# Power.net
KiCad netlist of a schematic drawn in Altium Designer
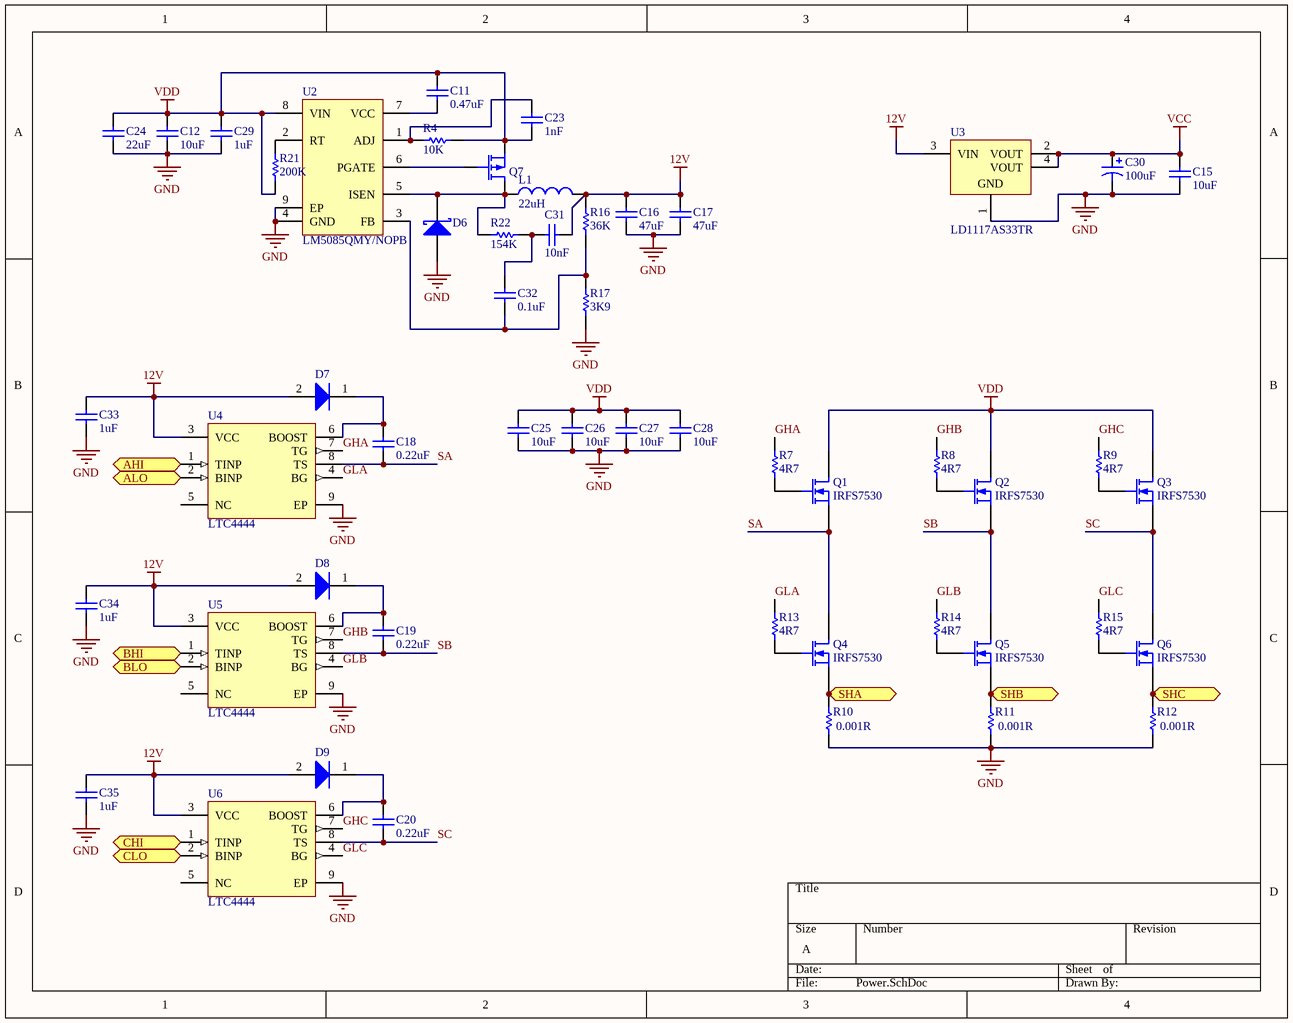
[diagram p0: Power.SchDoc]

(export (version "E")
  (design (tool "Eeschema 10.0.6"))
  (components
    (comp (ref "C11")
      (value "0.47uF")
      (footprint "CAPC0603(1608)100_N")
      (description "CAP 470nF 50V ±10% 0603 (1608 Metric) Thickness 1mm SMD")
      (fields (field (name "TOLERANCE") "Â±10%"))
      (libsource (lib "Altium Content Vault") (part "CAP"))
    )
    (comp (ref "C12")
      (value "10uF")
      (footprint "CAPC1206(3216)190_M")
      (description "CAP 10uF 50V Â±10% 1206 (3216 Metric) Thickness 1.9mm SMD")
      (fields (field (name "TOLERANCE") "Â±10%"))
      (libsource (lib "Altium Content Vault") (part "CMP-1037-04982-1"))
    )
    (comp (ref "C15")
      (value "10uF")
      (footprint "CAPC0402(1005)60_N")
      (description "CAP 10uF 6.3V ±20% 0402 (1005 Metric) Thickness 0.6mm SMD")
      (fields (field (name "TOLERANCE") "Â±20%"))
      (libsource (lib "Altium Content Vault") (part "CMP-1034-02138-1"))
    )
    (comp (ref "C16")
      (value "47uF")
      (footprint "CAPC1210(3225)280_N")
      (description "CAP 47uF 16V ±10% 1210 (3225 Metric) Thickness 2.8mm SMD")
      (fields (field (name "TOLERANCE") "Â±10%"))
      (libsource (lib "Altium Content Vault") (part "CAP"))
    )
    (comp (ref "C17")
      (value "47uF")
      (footprint "CAPC1210(3225)280_N")
      (description "CAP 47uF 16V ±10% 1210 (3225 Metric) Thickness 2.8mm SMD")
      (fields (field (name "TOLERANCE") "Â±10%"))
      (libsource (lib "Altium Content Vault") (part "CAP"))
    )
    (comp (ref "C18")
      (value "0.22uF")
      (footprint "CAPC0603(1608)100_N")
      (description "CAP 1uF 16V ±5% 0603 (1608 Metric) Thickness 1mm SMD")
      (fields (field (name "TOLERANCE") "Â±5%"))
      (libsource (lib "Altium Content Vault") (part "CMP-1035-02736-1"))
    )
    (comp (ref "C19")
      (value "0.22uF")
      (footprint "CAPC0603(1608)100_N")
      (description "CAP 1uF 16V ±5% 0603 (1608 Metric) Thickness 1mm SMD")
      (fields (field (name "TOLERANCE") "Â±5%"))
      (libsource (lib "Altium Content Vault") (part "CMP-1035-02736-1"))
    )
    (comp (ref "C20")
      (value "0.22uF")
      (footprint "CAPC0603(1608)100_N")
      (description "CAP 1uF 16V ±5% 0603 (1608 Metric) Thickness 1mm SMD")
      (fields (field (name "TOLERANCE") "Â±5%"))
      (libsource (lib "Altium Content Vault") (part "CMP-1035-02736-1"))
    )
    (comp (ref "C23")
      (value "1nF")
      (footprint "CAPC0402(1005)60_N")
      (description "CAP 1nF 50V ±1% 0402 (1005 Metric) Thickness 0.6mm SMD")
      (fields (field (name "TOLERANCE") "Â±1%"))
      (libsource (lib "Altium Content Vault") (part "CMP-1034-01624-1"))
    )
    (comp (ref "C24")
      (value "22uF")
      (footprint "CAPC2220(5750)230_N")
      (description "CAP 22uF 50V -20% to +80% 2220 (5750 Metric) Thickness 2.2mm SMD")
      (fields (field (name "TOLERANCE") "-20% to +80%"))
      (libsource (lib "Altium Content Vault") (part "CAP"))
    )
    (comp (ref "C25")
      (value "10uF")
      (footprint "CAPC1206(3216)190_M")
      (description "CAP 10uF 50V Â±10% 1206 (3216 Metric) Thickness 1.9mm SMD")
      (fields (field (name "TOLERANCE") "Â±10%"))
      (libsource (lib "Altium Content Vault") (part "CMP-1037-04982-1"))
    )
    (comp (ref "C26")
      (value "10uF")
      (footprint "CAPC1206(3216)190_M")
      (description "CAP 10uF 50V Â±10% 1206 (3216 Metric) Thickness 1.9mm SMD")
      (fields (field (name "TOLERANCE") "Â±10%"))
      (libsource (lib "Altium Content Vault") (part "CAP"))
    )
    (comp (ref "C27")
      (value "10uF")
      (footprint "CAPC1206(3216)190_M")
      (description "CAP 10uF 50V Â±10% 1206 (3216 Metric) Thickness 1.9mm SMD")
      (fields (field (name "TOLERANCE") "Â±10%"))
      (libsource (lib "Altium Content Vault") (part "CAP"))
    )
    (comp (ref "C28")
      (value "10uF")
      (footprint "CAPC1206(3216)190_M")
      (description "CAP 10uF 50V Â±10% 1206 (3216 Metric) Thickness 1.9mm SMD")
      (fields (field (name "TOLERANCE") "Â±10%"))
      (libsource (lib "Altium Content Vault") (part "CMP-1037-04982-1"))
    )
    (comp (ref "C29")
      (value "1uF")
      (footprint "CAPC0603(1608)100_L")
      (description "CAP 1uF 50V ±10% 0603 (1608 Metric) Thickness 1mm SMD")
      (fields (field (name "TOLERANCE") "Â±10%"))
      (libsource (lib "Altium Content Vault") (part "CAP"))
    )
    (comp (ref "C30")
      (value "100uF")
      (footprint "AVX-CAPC7343_V")
      (libsource (lib "Components") (part "AVX-CAP-P-2"))
    )
    (comp (ref "C31")
      (value "10nF")
      (footprint "CAPC0402(1005)60_L")
      (description "CAP 10nF 50V ±5% 0402 (1005 Metric) Thickness 0.6mm SMD")
      (fields (field (name "TOLERANCE") "Â±5%"))
      (libsource (lib "Altium Content Vault") (part "CAP"))
    )
    (comp (ref "C32")
      (value "0.1uF")
      (footprint "CAPC0402(1005)60_M")
      (description "CAP 100nF 50V ±10% 0402 (1005 Metric) Thickness 0.6mm SMD")
      (fields (field (name "TOLERANCE") "Â±10%"))
      (libsource (lib "Altium Content Vault") (part "CMP-1034-02077-1"))
    )
    (comp (ref "C33")
      (value "1uF")
      (footprint "CAPC0402(1005)60_M")
      (description "CAP 1uF 16V ±10% 0402 (1005 Metric) Thickness 0.6mm SMD")
      (fields (field (name "TOLERANCE") "Â±10%"))
      (libsource (lib "Altium Content Vault") (part "CMP-1034-02119-1"))
    )
    (comp (ref "C34")
      (value "1uF")
      (footprint "CAPC0402(1005)60_M")
      (description "CAP 1uF 16V ±10% 0402 (1005 Metric) Thickness 0.6mm SMD")
      (fields (field (name "TOLERANCE") "Â±10%"))
      (libsource (lib "Altium Content Vault") (part "CMP-1034-02119-1"))
    )
    (comp (ref "C35")
      (value "1uF")
      (footprint "CAPC0402(1005)60_M")
      (description "CAP 1uF 16V ±10% 0402 (1005 Metric) Thickness 0.6mm SMD")
      (fields (field (name "TOLERANCE") "Â±10%"))
      (libsource (lib "Altium Content Vault") (part "CMP-1034-02119-1"))
    )
    (comp (ref "D6")
      (value "~")
      (footprint "SMB")
      (description "Schottky Diode")
      (fields (field (name "PUBLISHER") "Altium Limited"))
      (libsource (lib "Miscellaneous Devices") (part "D Schottky"))
    )
    (comp (ref "D7")
      (value "~")
      (footprint "ONSC-SOD-323-2-477-02_V")
      (description "Silicon Hot-Carrier Diode, Schottky Barrier Diode, 2-Pin SOD-323, Pb-Free, Tape and Reel")
      (fields (field (name "PARTNUMBER") "MMDL301T1G") (field (name "MANUFACTURER") "On Semiconductor"))
      (libsource (lib "Altium Content Vault") (part "CMP-1051-00017-1"))
    )
    (comp (ref "D8")
      (value "~")
      (footprint "ONSC-SOD-323-2-477-02_V")
      (description "Silicon Hot-Carrier Diode, Schottky Barrier Diode, 2-Pin SOD-323, Pb-Free, Tape and Reel")
      (fields (field (name "PARTNUMBER") "MMDL301T1G") (field (name "MANUFACTURER") "On Semiconductor"))
      (libsource (lib "Altium Content Vault") (part "CMP-1051-00017-1"))
    )
    (comp (ref "D9")
      (value "~")
      (footprint "ONSC-SOD-323-2-477-02_V")
      (description "Silicon Hot-Carrier Diode, Schottky Barrier Diode, 2-Pin SOD-323, Pb-Free, Tape and Reel")
      (fields (field (name "PARTNUMBER") "MMDL301T1G") (field (name "MANUFACTURER") "On Semiconductor"))
      (libsource (lib "Altium Content Vault") (part "CMP-1051-00017-1"))
    )
    (comp (ref "L1")
      (value "22uH")
      (footprint "IHLP-4040DZ-51")
      (description "Inductor")
      (fields (field (name "Comment") "SDR0805-180ML") (field (name "PUBLISHER") "Altium Limited"))
      (libsource (lib "Components") (part "SDR0805-180ML"))
    )
    (comp (ref "Q1")
      (value "IRFS7530")
      (footprint "DPAK127P1525X483-7N")
      (description "N-Channel MOSFET")
      (fields (field (name "PUBLISHER") "Altium Limited"))
      (libsource (lib "Components") (part "IRFS7530"))
    )
    (comp (ref "Q2")
      (value "IRFS7530")
      (footprint "DPAK127P1525X483-7N")
      (description "N-Channel MOSFET")
      (fields (field (name "PUBLISHER") "Altium Limited"))
      (libsource (lib "Components") (part "IRFS7530"))
    )
    (comp (ref "Q3")
      (value "IRFS7530")
      (footprint "DPAK127P1525X483-7N")
      (description "N-Channel MOSFET")
      (fields (field (name "PUBLISHER") "Altium Limited"))
      (libsource (lib "Components") (part "IRFS7530"))
    )
    (comp (ref "Q4")
      (value "IRFS7530")
      (footprint "DPAK127P1525X483-7N")
      (description "N-Channel MOSFET")
      (fields (field (name "PUBLISHER") "Altium Limited"))
      (libsource (lib "Components") (part "IRFS7530"))
    )
    (comp (ref "Q5")
      (value "IRFS7530")
      (footprint "DPAK127P1525X483-7N")
      (description "N-Channel MOSFET")
      (fields (field (name "PUBLISHER") "Altium Limited"))
      (libsource (lib "Components") (part "IRFS7530"))
    )
    (comp (ref "Q6")
      (value "IRFS7530")
      (footprint "DPAK127P1525X483-7N")
      (description "N-Channel MOSFET")
      (fields (field (name "PUBLISHER") "Altium Limited"))
      (libsource (lib "Components") (part "IRFS7530"))
    )
    (comp (ref "Q7")
      (value "MOSFET-P")
      (footprint "SOIC127P600X175-8N")
      (description "P-Channel MOSFET")
      (fields (field (name "PUBLISHER") "Altium Limited"))
      (libsource (lib "Components") (part "MOSFET-P"))
    )
    (comp (ref "R4")
      (value "10K")
      (footprint "RESC0402(1005)_L")
      (description "10K 0.063W 1% 0402 (1005 Metric)  SMD")
      (fields (field (name "TOLERANCE") "1 %") (field (name "POWER") "0.063 W"))
      (libsource (lib "Altium Content Vault") (part "CMP-1011-00623-1"))
    )
    (comp (ref "R7")
      (value "4R7")
      (footprint "RESC0603(1608)_N")
      (description "4R7 0.1W 5% 0603 (1608 Metric)  SMD")
      (fields (field (name "POWER") "0.1 W") (field (name "TOLERANCE") "5 %"))
      (libsource (lib "Altium Content Vault") (part "CMP-1012-00018-1"))
    )
    (comp (ref "R8")
      (value "4R7")
      (footprint "RESC0603(1608)_N")
      (description "4R7 0.1W 5% 0603 (1608 Metric)  SMD")
      (fields (field (name "POWER") "0.1 W") (field (name "TOLERANCE") "5 %"))
      (libsource (lib "Altium Content Vault") (part "CMP-1012-00018-1"))
    )
    (comp (ref "R9")
      (value "4R7")
      (footprint "RESC0603(1608)_N")
      (description "4R7 0.1W 5% 0603 (1608 Metric)  SMD")
      (fields (field (name "POWER") "0.1 W") (field (name "TOLERANCE") "5 %"))
      (libsource (lib "Altium Content Vault") (part "CMP-1012-00018-1"))
    )
    (comp (ref "R10")
      (value "0.001R")
      (footprint "Shunt")
      (fields (field (name "PUBLISHER") "Altium Limited"))
      (libsource (lib "Components") (part "Shunt"))
    )
    (comp (ref "R11")
      (value "0.001R")
      (footprint "Shunt")
      (fields (field (name "PUBLISHER") "Altium Limited"))
      (libsource (lib "Components") (part "Shunt"))
    )
    (comp (ref "R12")
      (value "0.001R")
      (footprint "Shunt")
      (description "Resistor")
      (fields (field (name "PUBLISHER") "Altium Limited"))
      (libsource (lib "Components") (part "Shunt"))
    )
    (comp (ref "R13")
      (value "4R7")
      (footprint "RESC0603(1608)_N")
      (description "4R7 0.1W 5% 0603 (1608 Metric)  SMD")
      (fields (field (name "POWER") "0.1 W") (field (name "TOLERANCE") "5 %"))
      (libsource (lib "Altium Content Vault") (part "CMP-1012-00018-1"))
    )
    (comp (ref "R14")
      (value "4R7")
      (footprint "RESC0603(1608)_N")
      (description "4R7 0.1W 5% 0603 (1608 Metric)  SMD")
      (fields (field (name "POWER") "0.1 W") (field (name "TOLERANCE") "5 %"))
      (libsource (lib "Altium Content Vault") (part "CMP-1012-00018-1"))
    )
    (comp (ref "R15")
      (value "4R7")
      (footprint "RESC0603(1608)_N")
      (description "4R7 0.1W 5% 0603 (1608 Metric)  SMD")
      (fields (field (name "POWER") "0.1 W") (field (name "TOLERANCE") "5 %"))
      (libsource (lib "Altium Content Vault") (part "CMP-1012-00018-1"))
    )
    (comp (ref "R16")
      (value "36K")
      (footprint "RESC0402(1005)_M")
      (description "36K 0.063W 1% 0402 (1005 Metric)  SMD")
      (fields (field (name "POWER") "0.063 W") (field (name "TOLERANCE") "1 %"))
      (libsource (lib "Altium Content Vault") (part "CMP-1011-00685-1"))
    )
    (comp (ref "R17")
      (value "3K9")
      (footprint "RESC0402(1005)_N")
      (description "3K9 0.063W 1% 0402 (1005 Metric)  SMD")
      (fields (field (name "TOLERANCE") "1 %") (field (name "POWER") "0.063 W"))
      (libsource (lib "Altium Content Vault") (part "CMP-1011-00576-1"))
    )
    (comp (ref "R21")
      (value "200K")
      (footprint "RESC0402(1005)_L")
      (description "200K 0.063W 1% 0402 (1005 Metric)  SMD")
      (fields (field (name "TOLERANCE") "1 %") (field (name "POWER") "0.063 W"))
      (libsource (lib "Altium Content Vault") (part "CMP-1011-00768-1"))
    )
    (comp (ref "R22")
      (value "154K")
      (footprint "RESC0402(1005)_N")
      (description "154K 0.063W 1% 0402 (1005 Metric)  SMD")
      (fields (field (name "POWER") "0.063 W") (field (name "TOLERANCE") "1 %"))
      (libsource (lib "Altium Content Vault") (part "RES"))
    )
    (comp (ref "U2")
      (value "LM5085QMY/NOPB")
      (footprint "MUY08A_N")
      (description "75V Constant On-Time PFET Buck Switching Controller, 8-pin eMSOP, Pb-Free")
      (fields (field (name "MANUFACTURER") "National Semiconductor"))
      (libsource (lib "Altium Content Vault") (part "PM-SWREG-LM5085-9"))
    )
    (comp (ref "U3")
      (value "LD1117AS33TR")
      (footprint "SOT-223_M")
      (description "1A, Low Drop Positive Voltage Regulator, 3.3V, 4-Pin SOT-223, Tape and Reel")
      (libsource (lib "Altium Content Vault") (part "PM-REG-LD1117-SOT4"))
    )
    (comp (ref "U4")
      (value "LTC4444")
      (footprint "LT-MS8E-8-EDP_L")
      (libsource (lib "Components") (part "LT-LTC444X-MS8E-8"))
    )
    (comp (ref "U5")
      (value "LTC4444")
      (footprint "LT-MS8E-8-EDP_L")
      (libsource (lib "Components") (part "LT-LTC444X-MS8E-8"))
    )
    (comp (ref "U6")
      (value "LTC4444")
      (footprint "LT-MS8E-8-EDP_L")
      (libsource (lib "Components") (part "LT-LTC444X-MS8E-8"))
    )
  )
  (nets
    (net (code "1") (name "/AHI") (class "Default")
      (node (ref "U4") (pin "1") (pinfunction "TINP_1") (pintype "input"))
    )
    (net (code "2") (name "/ALO") (class "Default")
      (node (ref "U4") (pin "2") (pinfunction "BINP_2") (pintype "input"))
    )
    (net (code "3") (name "/BHI") (class "Default")
      (node (ref "U5") (pin "1") (pinfunction "TINP_1") (pintype "input"))
    )
    (net (code "4") (name "/BLO") (class "Default")
      (node (ref "U5") (pin "2") (pinfunction "BINP_2") (pintype "input"))
    )
    (net (code "5") (name "/CHI") (class "Default")
      (node (ref "U6") (pin "1") (pinfunction "TINP_1") (pintype "input"))
    )
    (net (code "6") (name "/CLO") (class "Default")
      (node (ref "U6") (pin "2") (pinfunction "BINP_2") (pintype "input"))
    )
    (net (code "7") (name "/GHA") (class "Default")
      (node (ref "R7") (pin "2") (pinfunction "2_2") (pintype "passive"))
      (node (ref "U4") (pin "7") (pinfunction "TG_7") (pintype "output"))
    )
    (net (code "8") (name "/GHB") (class "Default")
      (node (ref "R8") (pin "2") (pinfunction "2_2") (pintype "passive"))
      (node (ref "U5") (pin "7") (pinfunction "TG_7") (pintype "output"))
    )
    (net (code "9") (name "/GHC") (class "Default")
      (node (ref "R9") (pin "2") (pinfunction "2_2") (pintype "passive"))
      (node (ref "U6") (pin "7") (pinfunction "TG_7") (pintype "output"))
    )
    (net (code "10") (name "/GLA") (class "Default")
      (node (ref "R13") (pin "2") (pinfunction "2_2") (pintype "passive"))
      (node (ref "U4") (pin "4") (pinfunction "BG_4") (pintype "output"))
    )
    (net (code "11") (name "/GLB") (class "Default")
      (node (ref "R14") (pin "2") (pinfunction "2_2") (pintype "passive"))
      (node (ref "U5") (pin "4") (pinfunction "BG_4") (pintype "output"))
    )
    (net (code "12") (name "/GLC") (class "Default")
      (node (ref "R15") (pin "2") (pinfunction "2_2") (pintype "passive"))
      (node (ref "U6") (pin "4") (pinfunction "BG_4") (pintype "output"))
    )
    (net (code "13") (name "/SA") (class "Default")
      (node (ref "C18") (pin "1") (pinfunction "1_1") (pintype "passive"))
      (node (ref "Q1") (pin "3") (pinfunction "S_3") (pintype "passive"))
      (node (ref "Q4") (pin "1") (pinfunction "D_1") (pintype "passive"))
      (node (ref "U4") (pin "8") (pinfunction "TS_8") (pintype "passive"))
    )
    (net (code "14") (name "/SB") (class "Default")
      (node (ref "C19") (pin "1") (pinfunction "1_1") (pintype "passive"))
      (node (ref "Q2") (pin "3") (pinfunction "S_3") (pintype "passive"))
      (node (ref "Q5") (pin "1") (pinfunction "D_1") (pintype "passive"))
      (node (ref "U5") (pin "8") (pinfunction "TS_8") (pintype "passive"))
    )
    (net (code "15") (name "/SC") (class "Default")
      (node (ref "C20") (pin "1") (pinfunction "1_1") (pintype "passive"))
      (node (ref "Q3") (pin "3") (pinfunction "S_3") (pintype "passive"))
      (node (ref "Q6") (pin "1") (pinfunction "D_1") (pintype "passive"))
      (node (ref "U6") (pin "8") (pinfunction "TS_8") (pintype "passive"))
    )
    (net (code "16") (name "/SHA") (class "Default")
      (node (ref "Q4") (pin "3") (pinfunction "S_3") (pintype "passive"))
      (node (ref "R10") (pin "2") (pinfunction "2_2") (pintype "passive"))
    )
    (net (code "17") (name "/SHB") (class "Default")
      (node (ref "Q5") (pin "3") (pinfunction "S_3") (pintype "passive"))
      (node (ref "R11") (pin "2") (pinfunction "2_2") (pintype "passive"))
    )
    (net (code "18") (name "/SHC") (class "Default")
      (node (ref "Q6") (pin "3") (pinfunction "S_3") (pintype "passive"))
      (node (ref "R12") (pin "2") (pinfunction "2_2") (pintype "passive"))
    )
    (net (code "19") (name "12V") (class "Default")
      (node (ref "C16") (pin "2") (pinfunction "2_2") (pintype "passive"))
      (node (ref "C17") (pin "2") (pinfunction "2_2") (pintype "passive"))
      (node (ref "C31") (pin "2") (pinfunction "2_2") (pintype "passive"))
      (node (ref "C33") (pin "2") (pinfunction "2_2") (pintype "passive"))
      (node (ref "C34") (pin "2") (pinfunction "2_2") (pintype "passive"))
      (node (ref "C35") (pin "2") (pinfunction "2_2") (pintype "passive"))
      (node (ref "D7") (pin "2") (pinfunction "A_2") (pintype "passive"))
      (node (ref "D8") (pin "2") (pinfunction "A_2") (pintype "passive"))
      (node (ref "D9") (pin "2") (pinfunction "A_2") (pintype "passive"))
      (node (ref "L1") (pin "2") (pinfunction "2_2") (pintype "passive"))
      (node (ref "R16") (pin "2") (pinfunction "2_2") (pintype "passive"))
      (node (ref "U3") (pin "3") (pinfunction "VIN_3") (pintype "power_in"))
      (node (ref "U4") (pin "3") (pinfunction "VCC_3") (pintype "power_in"))
      (node (ref "U5") (pin "3") (pinfunction "VCC_3") (pintype "power_in"))
      (node (ref "U6") (pin "3") (pinfunction "VCC_3") (pintype "power_in"))
    )
    (net (code "20") (name "GND") (class "Default")
      (node (ref "C12") (pin "1") (pinfunction "1_1") (pintype "passive"))
      (node (ref "C15") (pin "1") (pinfunction "1_1") (pintype "passive"))
      (node (ref "C16") (pin "1") (pinfunction "1_1") (pintype "passive"))
      (node (ref "C17") (pin "1") (pinfunction "1_1") (pintype "passive"))
      (node (ref "C24") (pin "1") (pinfunction "1_1") (pintype "passive"))
      (node (ref "C25") (pin "1") (pinfunction "1_1") (pintype "passive"))
      (node (ref "C26") (pin "1") (pinfunction "1_1") (pintype "passive"))
      (node (ref "C27") (pin "1") (pinfunction "1_1") (pintype "passive"))
      (node (ref "C28") (pin "1") (pinfunction "1_1") (pintype "passive"))
      (node (ref "C29") (pin "1") (pinfunction "1_1") (pintype "passive"))
      (node (ref "C30") (pin "2") (pinfunction "2_2") (pintype "passive"))
      (node (ref "C33") (pin "1") (pinfunction "1_1") (pintype "passive"))
      (node (ref "C34") (pin "1") (pinfunction "1_1") (pintype "passive"))
      (node (ref "C35") (pin "1") (pinfunction "1_1") (pintype "passive"))
      (node (ref "D6") (pin "1") (pinfunction "A_1") (pintype "passive"))
      (node (ref "R10") (pin "1") (pinfunction "1_1") (pintype "passive"))
      (node (ref "R11") (pin "1") (pinfunction "1_1") (pintype "passive"))
      (node (ref "R12") (pin "1") (pinfunction "1_1") (pintype "passive"))
      (node (ref "R17") (pin "1") (pinfunction "1_1") (pintype "passive"))
      (node (ref "U2") (pin "4") (pinfunction "GND_4") (pintype "power_in"))
      (node (ref "U2") (pin "9") (pinfunction "EP_9") (pintype "passive"))
      (node (ref "U3") (pin "1") (pinfunction "GND_1") (pintype "power_in"))
      (node (ref "U4") (pin "9") (pinfunction "EP_9") (pintype "power_in"))
      (node (ref "U5") (pin "9") (pinfunction "EP_9") (pintype "power_in"))
      (node (ref "U6") (pin "9") (pinfunction "EP_9") (pintype "power_in"))
    )
    (net (code "21") (name "Net-(C31-Pad1)") (class "Default")
      (node (ref "C31") (pin "1") (pinfunction "1_1") (pintype "passive"))
      (node (ref "C32") (pin "2") (pinfunction "2_2") (pintype "passive"))
      (node (ref "R22") (pin "2") (pinfunction "2_2") (pintype "passive"))
    )
    (net (code "22") (name "Net-(D6-K)") (class "Default")
      (node (ref "D6") (pin "2") (pinfunction "K_2") (pintype "passive"))
      (node (ref "L1") (pin "1") (pinfunction "1_1") (pintype "passive"))
      (node (ref "Q7") (pin "2") (pinfunction "D_2") (pintype "passive"))
      (node (ref "R22") (pin "1") (pinfunction "1_1") (pintype "passive"))
      (node (ref "U2") (pin "5") (pinfunction "ISEN_5") (pintype "passive"))
    )
    (net (code "23") (name "Net-(D7-K)") (class "Default")
      (node (ref "C18") (pin "2") (pinfunction "2_2") (pintype "passive"))
      (node (ref "D7") (pin "1") (pinfunction "K_1") (pintype "passive"))
      (node (ref "U4") (pin "6") (pinfunction "BOOST_6") (pintype "passive"))
    )
    (net (code "24") (name "Net-(D8-K)") (class "Default")
      (node (ref "C19") (pin "2") (pinfunction "2_2") (pintype "passive"))
      (node (ref "D8") (pin "1") (pinfunction "K_1") (pintype "passive"))
      (node (ref "U5") (pin "6") (pinfunction "BOOST_6") (pintype "passive"))
    )
    (net (code "25") (name "Net-(D9-K)") (class "Default")
      (node (ref "C20") (pin "2") (pinfunction "2_2") (pintype "passive"))
      (node (ref "D9") (pin "1") (pinfunction "K_1") (pintype "passive"))
      (node (ref "U6") (pin "6") (pinfunction "BOOST_6") (pintype "passive"))
    )
    (net (code "26") (name "Net-(Q1-G)") (class "Default")
      (node (ref "Q1") (pin "2") (pinfunction "G_2") (pintype "passive"))
      (node (ref "R7") (pin "1") (pinfunction "1_1") (pintype "passive"))
    )
    (net (code "27") (name "Net-(Q2-G)") (class "Default")
      (node (ref "Q2") (pin "2") (pinfunction "G_2") (pintype "passive"))
      (node (ref "R8") (pin "1") (pinfunction "1_1") (pintype "passive"))
    )
    (net (code "28") (name "Net-(Q3-G)") (class "Default")
      (node (ref "Q3") (pin "2") (pinfunction "G_2") (pintype "passive"))
      (node (ref "R9") (pin "1") (pinfunction "1_1") (pintype "passive"))
    )
    (net (code "29") (name "Net-(Q4-G)") (class "Default")
      (node (ref "Q4") (pin "2") (pinfunction "G_2") (pintype "passive"))
      (node (ref "R13") (pin "1") (pinfunction "1_1") (pintype "passive"))
    )
    (net (code "30") (name "Net-(Q5-G)") (class "Default")
      (node (ref "Q5") (pin "2") (pinfunction "G_2") (pintype "passive"))
      (node (ref "R14") (pin "1") (pinfunction "1_1") (pintype "passive"))
    )
    (net (code "31") (name "Net-(Q6-G)") (class "Default")
      (node (ref "Q6") (pin "2") (pinfunction "G_2") (pintype "passive"))
      (node (ref "R15") (pin "1") (pinfunction "1_1") (pintype "passive"))
    )
    (net (code "32") (name "Net-(Q7-G)") (class "Default")
      (node (ref "Q7") (pin "1") (pinfunction "G_1") (pintype "passive"))
      (node (ref "U2") (pin "6") (pinfunction "PGATE_6") (pintype "passive"))
    )
    (net (code "33") (name "Net-(U2-ADJ)") (class "Default")
      (node (ref "C23") (pin "2") (pinfunction "2_2") (pintype "passive"))
      (node (ref "R4") (pin "1") (pinfunction "1_1") (pintype "passive"))
      (node (ref "U2") (pin "1") (pinfunction "ADJ_1") (pintype "passive"))
    )
    (net (code "34") (name "Net-(U2-FB)") (class "Default")
      (node (ref "C32") (pin "1") (pinfunction "1_1") (pintype "passive"))
      (node (ref "R16") (pin "1") (pinfunction "1_1") (pintype "passive"))
      (node (ref "R17") (pin "2") (pinfunction "2_2") (pintype "passive"))
      (node (ref "U2") (pin "3") (pinfunction "FB_3") (pintype "passive"))
    )
    (net (code "35") (name "Net-(U2-RT)") (class "Default")
      (node (ref "R21") (pin "2") (pinfunction "2_2") (pintype "passive"))
      (node (ref "U2") (pin "2") (pinfunction "RT_2") (pintype "passive"))
    )
    (net (code "36") (name "Net-(U2-VCC)") (class "Default")
      (node (ref "C11") (pin "1") (pinfunction "1_1") (pintype "passive"))
      (node (ref "U2") (pin "7") (pinfunction "VCC_7") (pintype "power_in"))
    )
    (net (code "37") (name "VCC") (class "Default")
      (node (ref "C15") (pin "2") (pinfunction "2_2") (pintype "passive"))
      (node (ref "C30") (pin "1") (pinfunction "1_1") (pintype "passive"))
      (node (ref "U3") (pin "2") (pinfunction "VOUT_2") (pintype "power_in"))
      (node (ref "U3") (pin "4") (pinfunction "VOUT_4") (pintype "power_in"))
    )
    (net (code "38") (name "VDD") (class "Default")
      (node (ref "C11") (pin "2") (pinfunction "2_2") (pintype "passive"))
      (node (ref "C12") (pin "2") (pinfunction "2_2") (pintype "passive"))
      (node (ref "C23") (pin "1") (pinfunction "1_1") (pintype "passive"))
      (node (ref "C24") (pin "2") (pinfunction "2_2") (pintype "passive"))
      (node (ref "C25") (pin "2") (pinfunction "2_2") (pintype "passive"))
      (node (ref "C26") (pin "2") (pinfunction "2_2") (pintype "passive"))
      (node (ref "C27") (pin "2") (pinfunction "2_2") (pintype "passive"))
      (node (ref "C28") (pin "2") (pinfunction "2_2") (pintype "passive"))
      (node (ref "C29") (pin "2") (pinfunction "2_2") (pintype "passive"))
      (node (ref "Q1") (pin "1") (pinfunction "D_1") (pintype "passive"))
      (node (ref "Q2") (pin "1") (pinfunction "D_1") (pintype "passive"))
      (node (ref "Q3") (pin "1") (pinfunction "D_1") (pintype "passive"))
      (node (ref "Q7") (pin "3") (pinfunction "S_3") (pintype "passive"))
      (node (ref "R21") (pin "1") (pinfunction "1_1") (pintype "passive"))
      (node (ref "R4") (pin "2") (pinfunction "2_2") (pintype "passive"))
      (node (ref "U2") (pin "8") (pinfunction "VIN_8") (pintype "passive"))
    )
    (net (code "39") (name "unconnected-(U4-NC-Pad5)") (class "Default")
      (node (ref "U4") (pin "5") (pinfunction "NC_5") (pintype "passive"))
    )
    (net (code "40") (name "unconnected-(U5-NC-Pad5)") (class "Default")
      (node (ref "U5") (pin "5") (pinfunction "NC_5") (pintype "passive"))
    )
    (net (code "41") (name "unconnected-(U6-NC-Pad5)") (class "Default")
      (node (ref "U6") (pin "5") (pinfunction "NC_5") (pintype "passive"))
    )
  )
)
